# Tapper.net
KiCad netlist of a schematic drawn in EAGLE
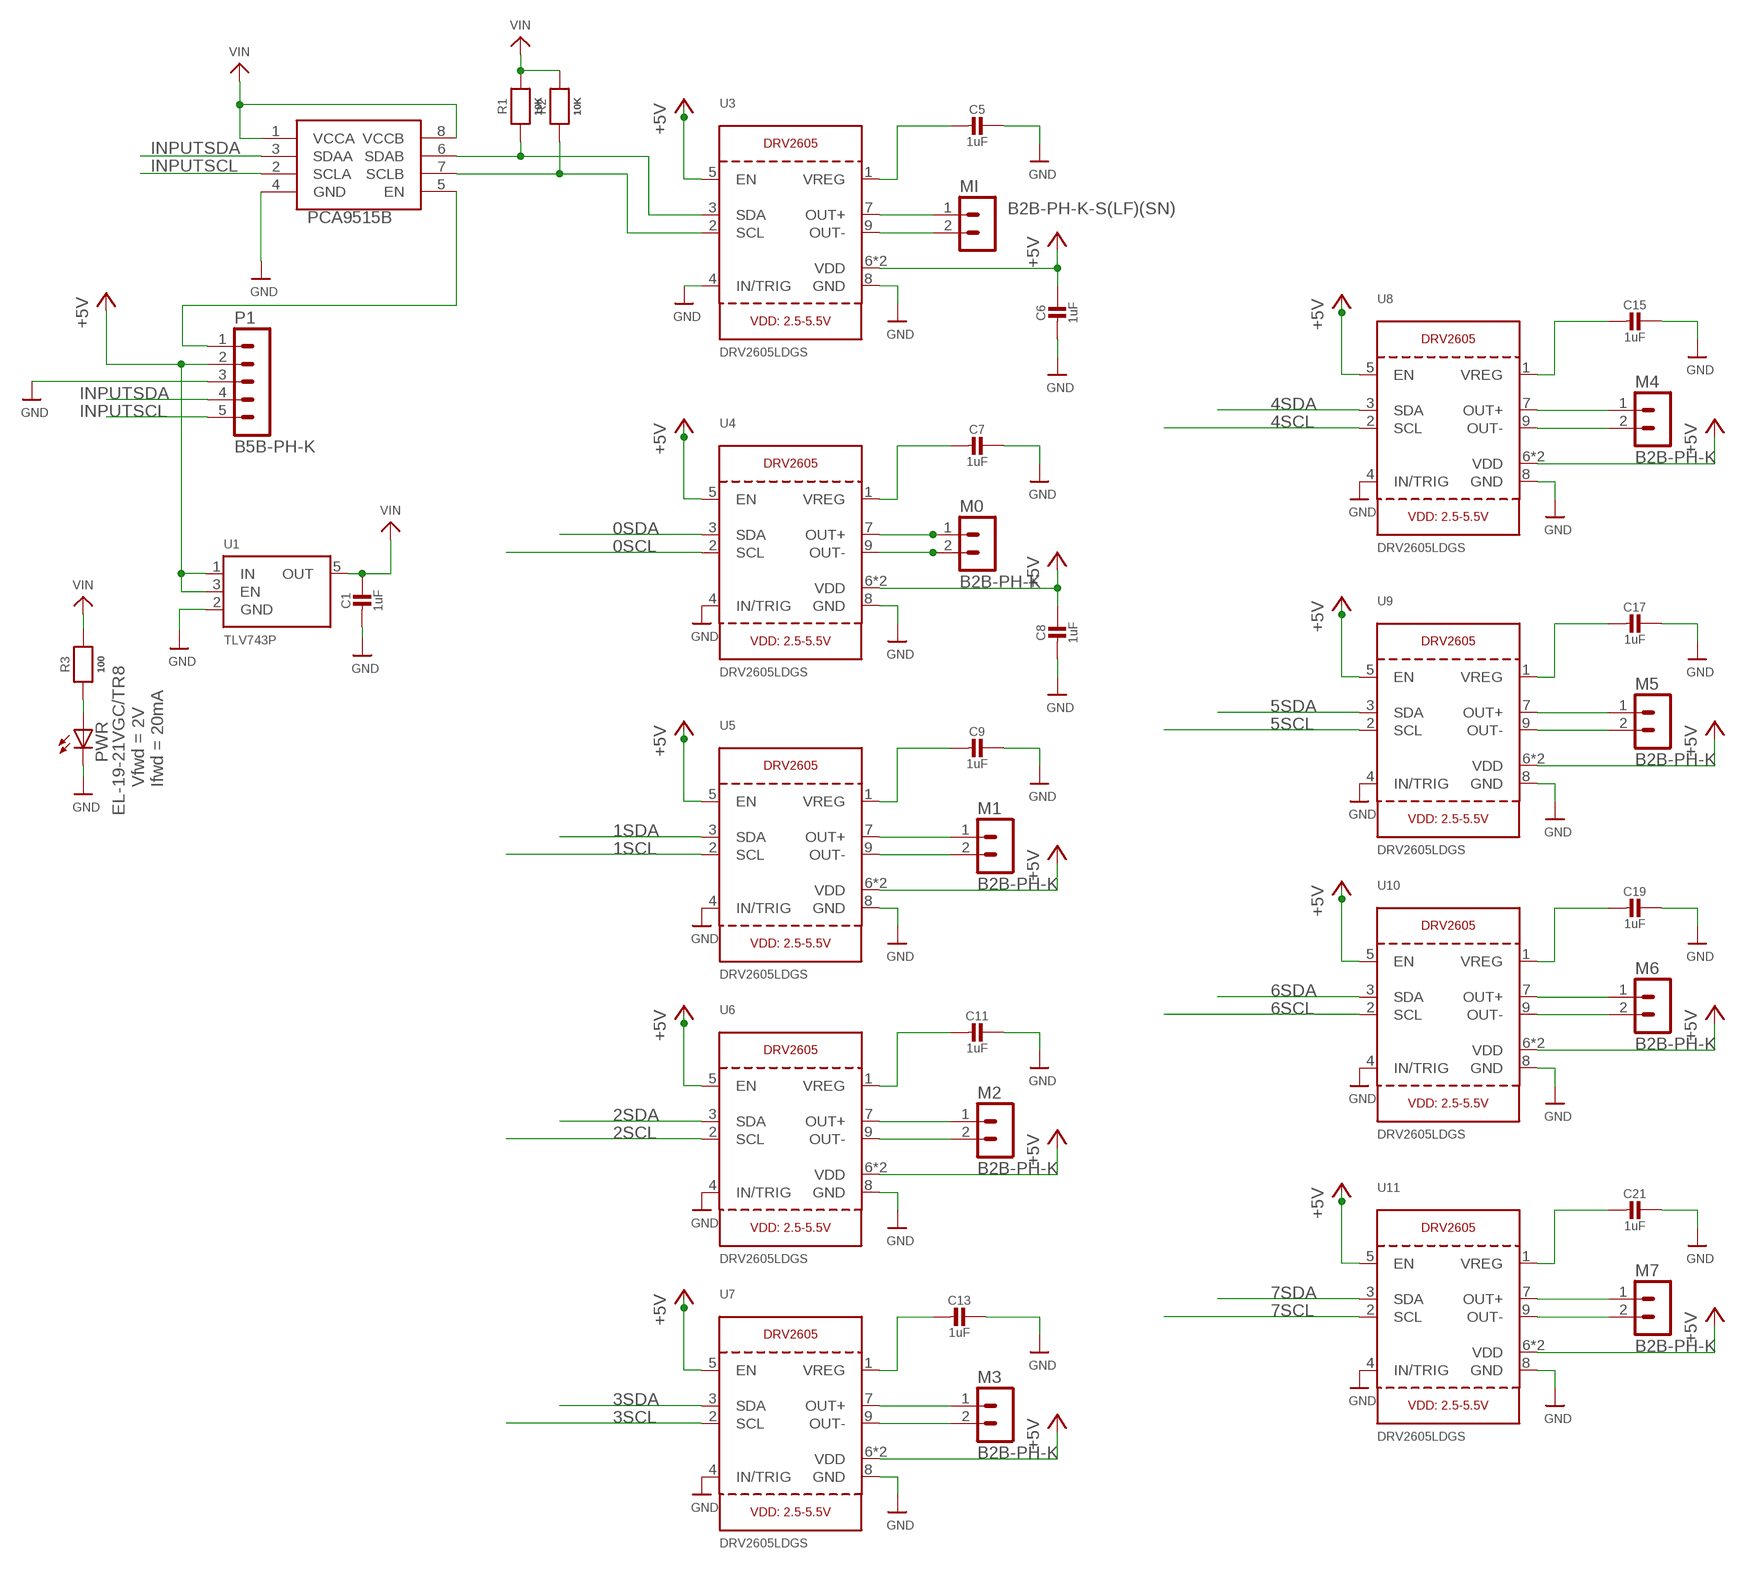
[diagram p0: schematic, sheet 1]
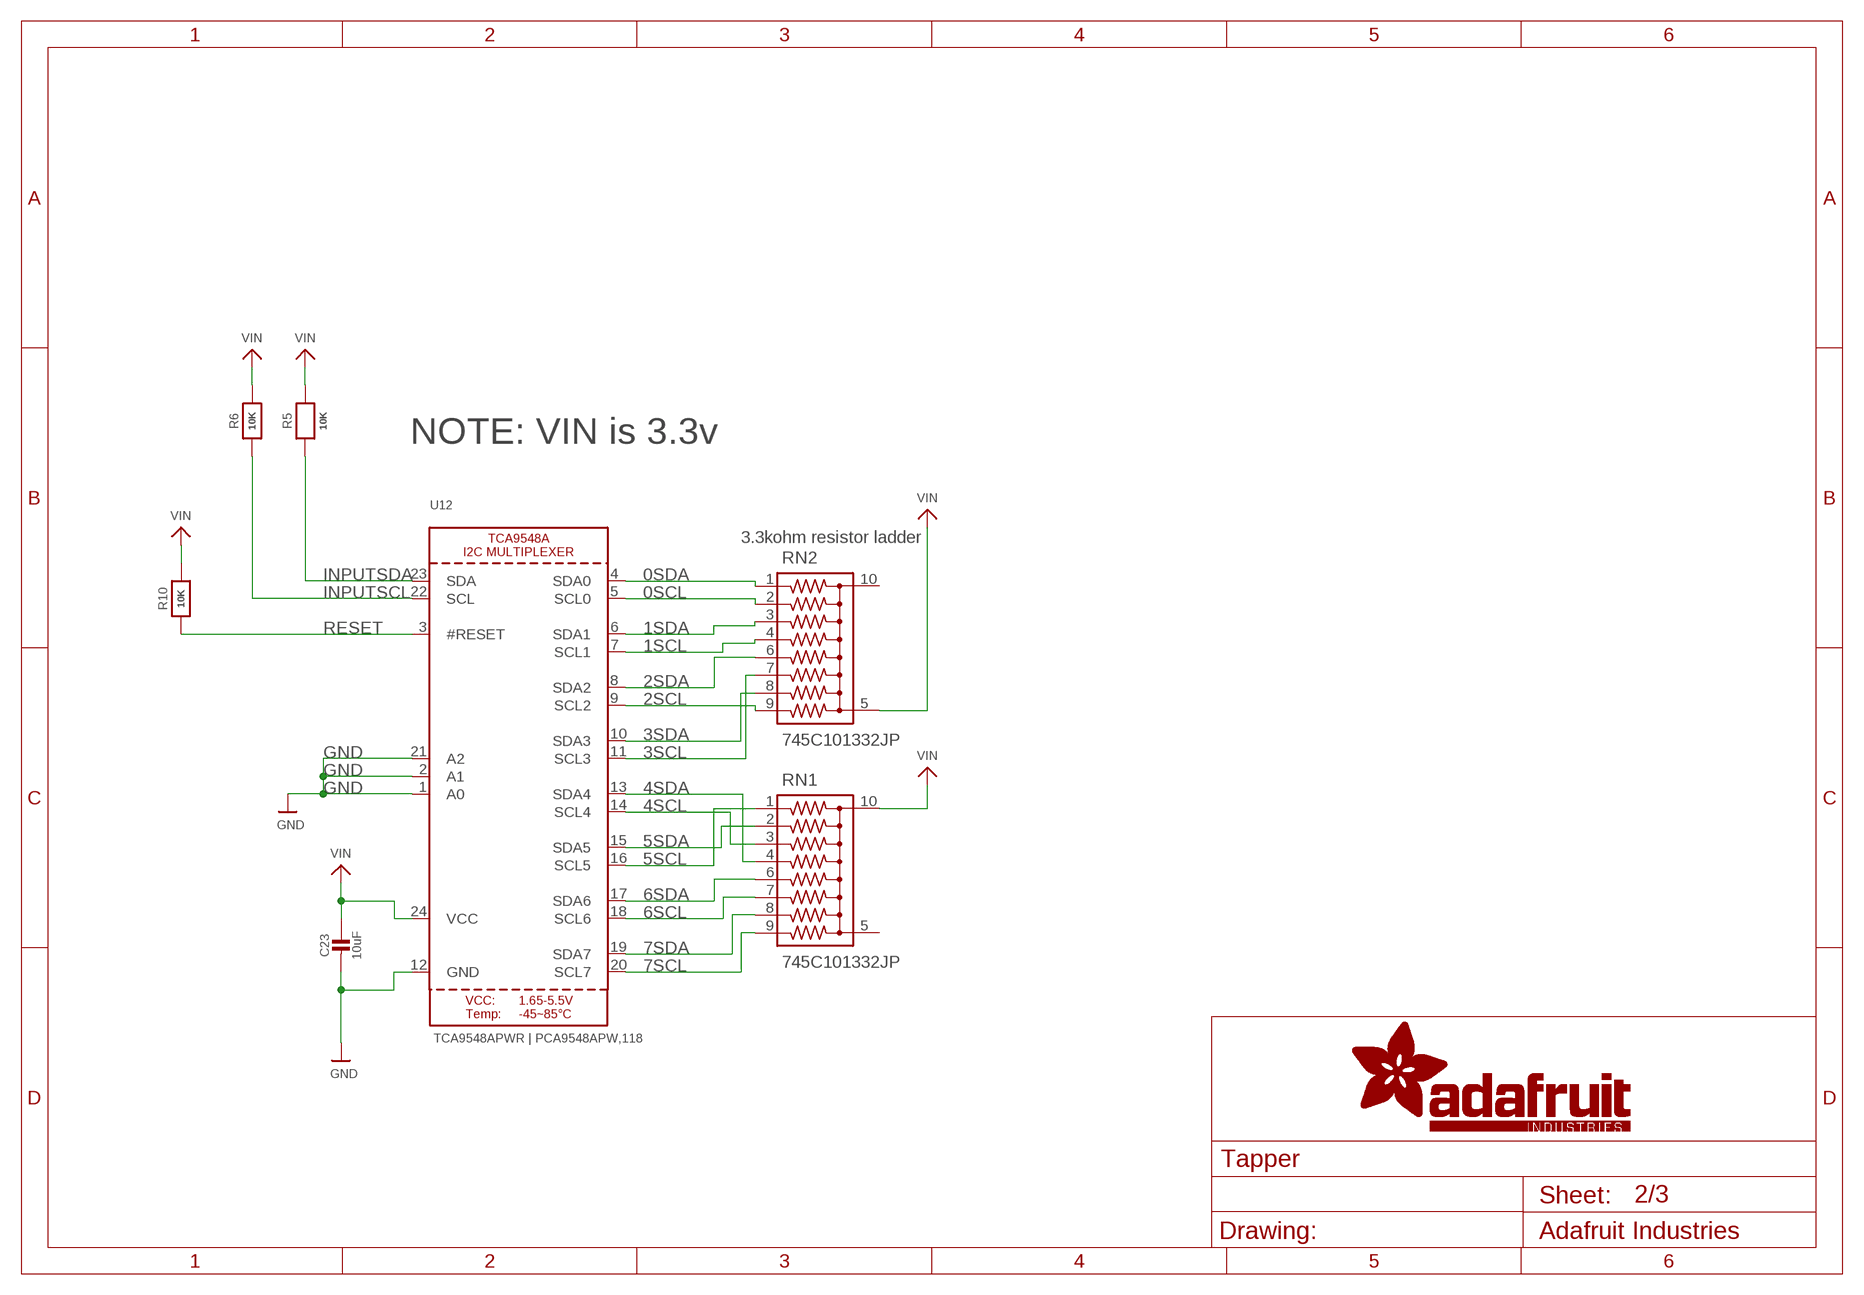
[diagram p1: schematic, sheet 2]

(export (version "E")
  (design (tool "Eeschema 10.0.6"))
  (components
    (comp (ref "C1")
      (value "1uF")
      (footprint "eagle-import:0805-NO")
      (libsource (lib "eagle-import") (part "CAP_CERAMIC0805-NOOUTLINE"))
    )
    (comp (ref "C5")
      (value "1uF")
      (footprint "eagle-import:0805-NO")
      (libsource (lib "eagle-import") (part "CAP_CERAMIC0805-NOOUTLINE"))
    )
    (comp (ref "C6")
      (value "1uF")
      (footprint "eagle-import:0805-NO")
      (libsource (lib "eagle-import") (part "CAP_CERAMIC0805-NOOUTLINE"))
    )
    (comp (ref "C7")
      (value "1uF")
      (footprint "eagle-import:0805-NO")
      (libsource (lib "eagle-import") (part "CAP_CERAMIC0805-NOOUTLINE"))
    )
    (comp (ref "C8")
      (value "1uF")
      (footprint "eagle-import:0805-NO")
      (libsource (lib "eagle-import") (part "CAP_CERAMIC0805-NOOUTLINE"))
    )
    (comp (ref "C9")
      (value "1uF")
      (footprint "eagle-import:0805-NO")
      (libsource (lib "eagle-import") (part "CAP_CERAMIC0805-NOOUTLINE"))
    )
    (comp (ref "C11")
      (value "1uF")
      (footprint "eagle-import:0805-NO")
      (libsource (lib "eagle-import") (part "CAP_CERAMIC0805-NOOUTLINE"))
    )
    (comp (ref "C13")
      (value "1uF")
      (footprint "eagle-import:0805-NO")
      (libsource (lib "eagle-import") (part "CAP_CERAMIC0805-NOOUTLINE"))
    )
    (comp (ref "C15")
      (value "1uF")
      (footprint "eagle-import:0805-NO")
      (libsource (lib "eagle-import") (part "CAP_CERAMIC0805-NOOUTLINE"))
    )
    (comp (ref "C17")
      (value "1uF")
      (footprint "eagle-import:0805-NO")
      (libsource (lib "eagle-import") (part "CAP_CERAMIC0805-NOOUTLINE"))
    )
    (comp (ref "C19")
      (value "1uF")
      (footprint "eagle-import:0805-NO")
      (libsource (lib "eagle-import") (part "CAP_CERAMIC0805-NOOUTLINE"))
    )
    (comp (ref "C21")
      (value "1uF")
      (footprint "eagle-import:0805-NO")
      (libsource (lib "eagle-import") (part "CAP_CERAMIC0805-NOOUTLINE"))
    )
    (comp (ref "M0")
      (value "B2B-PH-K")
      (footprint "eagle-import:B2B-PH-K")
      (libsource (lib "eagle-import") (part "B2B-PH-K"))
    )
    (comp (ref "M1")
      (value "B2B-PH-K")
      (footprint "eagle-import:B2B-PH-K")
      (libsource (lib "eagle-import") (part "B2B-PH-K"))
    )
    (comp (ref "M2")
      (value "B2B-PH-K")
      (footprint "eagle-import:B2B-PH-K")
      (libsource (lib "eagle-import") (part "B2B-PH-K"))
    )
    (comp (ref "M3")
      (value "B2B-PH-K")
      (footprint "eagle-import:B2B-PH-K")
      (libsource (lib "eagle-import") (part "B2B-PH-K"))
    )
    (comp (ref "M4")
      (value "B2B-PH-K")
      (footprint "eagle-import:B2B-PH-K")
      (libsource (lib "eagle-import") (part "B2B-PH-K"))
    )
    (comp (ref "M5")
      (value "B2B-PH-K")
      (footprint "eagle-import:B2B-PH-K")
      (libsource (lib "eagle-import") (part "B2B-PH-K"))
    )
    (comp (ref "M6")
      (value "B2B-PH-K")
      (footprint "eagle-import:B2B-PH-K")
      (libsource (lib "eagle-import") (part "B2B-PH-K"))
    )
    (comp (ref "M7")
      (value "B2B-PH-K")
      (footprint "eagle-import:B2B-PH-K")
      (libsource (lib "eagle-import") (part "B2B-PH-K"))
    )
    (comp (ref "MI")
      (value "B2B-PH-K-S(LF)(SN)")
      (footprint "eagle-import:B2B-PH-K")
      (libsource (lib "eagle-import") (part "B2B-PH-K"))
    )
    (comp (ref "P1")
      (value "B5B-PH-K")
      (footprint "eagle-import:B5B-PH-K")
      (libsource (lib "eagle-import") (part "B5B-PH-K"))
    )
    (comp (ref "PWR")
      (value "EL-19-21VGC/TR8")
      (footprint "eagle-import:CHIP-LED0603")
      (libsource (lib "eagle-import") (part "LEDCHIP-LED0603"))
    )
    (comp (ref "R1")
      (value "10K")
      (footprint "eagle-import:0805-NO")
      (libsource (lib "eagle-import") (part "RESISTOR0805_NOOUTLINE"))
    )
    (comp (ref "R2")
      (value "10K")
      (footprint "eagle-import:0805-NO")
      (libsource (lib "eagle-import") (part "RESISTOR0805_NOOUTLINE"))
    )
    (comp (ref "R3")
      (value "100")
      (footprint "eagle-import:0805-NO")
      (libsource (lib "eagle-import") (part "RESISTOR0805_NOOUTLINE"))
    )
    (comp (ref "U1")
      (value "TLV743P")
      (footprint "eagle-import:SOT23-5")
      (libsource (lib "eagle-import") (part "LD39015XX"))
    )
    (comp (ref "U3")
      (value "DRV2605LDGS")
      (footprint "eagle-import:PSOP10")
      (libsource (lib "eagle-import") (part "DRV2605_SOP"))
    )
    (comp (ref "U4")
      (value "DRV2605LDGS")
      (footprint "eagle-import:PSOP10")
      (libsource (lib "eagle-import") (part "DRV2605_SOP"))
    )
    (comp (ref "U5")
      (value "DRV2605LDGS")
      (footprint "eagle-import:PSOP10")
      (libsource (lib "eagle-import") (part "DRV2605_SOP"))
    )
    (comp (ref "U6")
      (value "DRV2605LDGS")
      (footprint "eagle-import:PSOP10")
      (libsource (lib "eagle-import") (part "DRV2605_SOP"))
    )
    (comp (ref "U7")
      (value "DRV2605LDGS")
      (footprint "eagle-import:PSOP10")
      (libsource (lib "eagle-import") (part "DRV2605_SOP"))
    )
    (comp (ref "U8")
      (value "DRV2605LDGS")
      (footprint "eagle-import:PSOP10")
      (libsource (lib "eagle-import") (part "DRV2605_SOP"))
    )
    (comp (ref "U9")
      (value "DRV2605LDGS")
      (footprint "eagle-import:PSOP10")
      (libsource (lib "eagle-import") (part "DRV2605_SOP"))
    )
    (comp (ref "U10")
      (value "DRV2605LDGS")
      (footprint "eagle-import:PSOP10")
      (libsource (lib "eagle-import") (part "DRV2605_SOP"))
    )
    (comp (ref "U11")
      (value "DRV2605LDGS")
      (footprint "eagle-import:PSOP10")
      (libsource (lib "eagle-import") (part "DRV2605_SOP"))
    )
    (comp (ref "U23")
      (value "PCA9515B")
      (footprint "eagle-import:SO-08")
      (libsource (lib "eagle-import") (part "PCA9517"))
    )
    (comp (ref "C23")
      (value "10uF")
      (footprint "eagle-import:0805-NO")
      (libsource (lib "eagle-import") (part "CAP_CERAMIC0805-NOOUTLINE"))
    )
    (comp (ref "R5")
      (value "10K")
      (footprint "eagle-import:0805-NO")
      (libsource (lib "eagle-import") (part "RESISTOR0805_NOOUTLINE"))
    )
    (comp (ref "R6")
      (value "10K")
      (footprint "eagle-import:0805-NO")
      (libsource (lib "eagle-import") (part "RESISTOR0805_NOOUTLINE"))
    )
    (comp (ref "R10")
      (value "10K")
      (footprint "eagle-import:_0805MP")
      (libsource (lib "eagle-import") (part "RESISTOR_0805MP"))
    )
    (comp (ref "RN1")
      (value "745C101332JP")
      (footprint "eagle-import:745-10NS")
      (libsource (lib "eagle-import") (part "745-10NS"))
    )
    (comp (ref "RN2")
      (value "745C101332JP")
      (footprint "eagle-import:745-10NS")
      (libsource (lib "eagle-import") (part "745-10NS"))
    )
    (comp (ref "U12")
      (value "TCA9548APWR | PCA9548APW,118")
      (footprint "eagle-import:TSSOP24")
      (libsource (lib "eagle-import") (part "TCA9548A"))
    )
  )
  (nets
    (net (code "1") (name "+5V") (class "Default")
      (node (ref "C6") (pin "1") (pinfunction "1_1") (pintype "passive"))
      (node (ref "C8") (pin "1") (pinfunction "1_1") (pintype "passive"))
      (node (ref "P1") (pin "2") (pinfunction "2_2") (pintype "passive"))
      (node (ref "U1") (pin "1") (pinfunction "IN_1") (pintype "bidirectional"))
      (node (ref "U1") (pin "3") (pinfunction "EN_3") (pintype "bidirectional"))
      (node (ref "U10") (pin "10") (pinfunction "VDD_10") (pintype "power_in"))
      (node (ref "U10") (pin "5") (pinfunction "EN_5") (pintype "input"))
      (node (ref "U10") (pin "6") (pinfunction "VDD_6") (pintype "power_in"))
      (node (ref "U11") (pin "10") (pinfunction "VDD_10") (pintype "power_in"))
      (node (ref "U11") (pin "5") (pinfunction "EN_5") (pintype "input"))
      (node (ref "U11") (pin "6") (pinfunction "VDD_6") (pintype "power_in"))
      (node (ref "U3") (pin "10") (pinfunction "VDD_10") (pintype "power_in"))
      (node (ref "U3") (pin "5") (pinfunction "EN_5") (pintype "input"))
      (node (ref "U3") (pin "6") (pinfunction "VDD_6") (pintype "power_in"))
      (node (ref "U4") (pin "10") (pinfunction "VDD_10") (pintype "power_in"))
      (node (ref "U4") (pin "5") (pinfunction "EN_5") (pintype "input"))
      (node (ref "U4") (pin "6") (pinfunction "VDD_6") (pintype "power_in"))
      (node (ref "U5") (pin "10") (pinfunction "VDD_10") (pintype "power_in"))
      (node (ref "U5") (pin "5") (pinfunction "EN_5") (pintype "input"))
      (node (ref "U5") (pin "6") (pinfunction "VDD_6") (pintype "power_in"))
      (node (ref "U6") (pin "10") (pinfunction "VDD_10") (pintype "power_in"))
      (node (ref "U6") (pin "5") (pinfunction "EN_5") (pintype "input"))
      (node (ref "U6") (pin "6") (pinfunction "VDD_6") (pintype "power_in"))
      (node (ref "U7") (pin "10") (pinfunction "VDD_10") (pintype "power_in"))
      (node (ref "U7") (pin "5") (pinfunction "EN_5") (pintype "input"))
      (node (ref "U7") (pin "6") (pinfunction "VDD_6") (pintype "power_in"))
      (node (ref "U8") (pin "10") (pinfunction "VDD_10") (pintype "power_in"))
      (node (ref "U8") (pin "5") (pinfunction "EN_5") (pintype "input"))
      (node (ref "U8") (pin "6") (pinfunction "VDD_6") (pintype "power_in"))
      (node (ref "U9") (pin "10") (pinfunction "VDD_10") (pintype "power_in"))
      (node (ref "U9") (pin "5") (pinfunction "EN_5") (pintype "input"))
      (node (ref "U9") (pin "6") (pinfunction "VDD_6") (pintype "power_in"))
    )
    (net (code "2") (name "0SCL") (class "Default")
      (node (ref "RN2") (pin "2") (pinfunction "2_2") (pintype "passive"))
      (node (ref "U12") (pin "5") (pinfunction "SCL0_5") (pintype "bidirectional"))
      (node (ref "U4") (pin "2") (pinfunction "SCL_2") (pintype "input"))
    )
    (net (code "3") (name "0SDA") (class "Default")
      (node (ref "RN2") (pin "1") (pinfunction "1_1") (pintype "passive"))
      (node (ref "U12") (pin "4") (pinfunction "SDA0_4") (pintype "bidirectional"))
      (node (ref "U4") (pin "3") (pinfunction "SDA_3") (pintype "bidirectional"))
    )
    (net (code "4") (name "1SCL") (class "Default")
      (node (ref "RN2") (pin "4") (pinfunction "4_4") (pintype "passive"))
      (node (ref "U12") (pin "7") (pinfunction "SCL1_7") (pintype "bidirectional"))
      (node (ref "U5") (pin "2") (pinfunction "SCL_2") (pintype "input"))
    )
    (net (code "5") (name "1SDA") (class "Default")
      (node (ref "RN2") (pin "3") (pinfunction "3_3") (pintype "passive"))
      (node (ref "U12") (pin "6") (pinfunction "SDA1_6") (pintype "bidirectional"))
      (node (ref "U5") (pin "3") (pinfunction "SDA_3") (pintype "bidirectional"))
    )
    (net (code "6") (name "2SCL") (class "Default")
      (node (ref "RN2") (pin "9") (pinfunction "9_9") (pintype "passive"))
      (node (ref "U12") (pin "9") (pinfunction "SCL2_9") (pintype "bidirectional"))
      (node (ref "U6") (pin "2") (pinfunction "SCL_2") (pintype "input"))
    )
    (net (code "7") (name "2SDA") (class "Default")
      (node (ref "RN2") (pin "6") (pinfunction "6_6") (pintype "passive"))
      (node (ref "U12") (pin "8") (pinfunction "SDA2_8") (pintype "bidirectional"))
      (node (ref "U6") (pin "3") (pinfunction "SDA_3") (pintype "bidirectional"))
    )
    (net (code "8") (name "3SCL") (class "Default")
      (node (ref "RN2") (pin "7") (pinfunction "7_7") (pintype "passive"))
      (node (ref "U12") (pin "11") (pinfunction "SCL3_11") (pintype "bidirectional"))
      (node (ref "U7") (pin "2") (pinfunction "SCL_2") (pintype "input"))
    )
    (net (code "9") (name "3SDA") (class "Default")
      (node (ref "RN2") (pin "8") (pinfunction "8_8") (pintype "passive"))
      (node (ref "U12") (pin "10") (pinfunction "SDA3_10") (pintype "bidirectional"))
      (node (ref "U7") (pin "3") (pinfunction "SDA_3") (pintype "bidirectional"))
    )
    (net (code "10") (name "4SCL") (class "Default")
      (node (ref "RN1") (pin "3") (pinfunction "3_3") (pintype "passive"))
      (node (ref "U12") (pin "14") (pinfunction "SCL4_14") (pintype "bidirectional"))
      (node (ref "U8") (pin "2") (pinfunction "SCL_2") (pintype "input"))
    )
    (net (code "11") (name "4SDA") (class "Default")
      (node (ref "RN1") (pin "4") (pinfunction "4_4") (pintype "passive"))
      (node (ref "U12") (pin "13") (pinfunction "SDA4_13") (pintype "bidirectional"))
      (node (ref "U8") (pin "3") (pinfunction "SDA_3") (pintype "bidirectional"))
    )
    (net (code "12") (name "5SCL") (class "Default")
      (node (ref "RN1") (pin "1") (pinfunction "1_1") (pintype "passive"))
      (node (ref "U12") (pin "16") (pinfunction "SCL5_16") (pintype "bidirectional"))
      (node (ref "U9") (pin "2") (pinfunction "SCL_2") (pintype "input"))
    )
    (net (code "13") (name "5SDA") (class "Default")
      (node (ref "RN1") (pin "2") (pinfunction "2_2") (pintype "passive"))
      (node (ref "U12") (pin "15") (pinfunction "SDA5_15") (pintype "bidirectional"))
      (node (ref "U9") (pin "3") (pinfunction "SDA_3") (pintype "bidirectional"))
    )
    (net (code "14") (name "6SCL") (class "Default")
      (node (ref "RN1") (pin "7") (pinfunction "7_7") (pintype "passive"))
      (node (ref "U10") (pin "2") (pinfunction "SCL_2") (pintype "input"))
      (node (ref "U12") (pin "18") (pinfunction "SCL6_18") (pintype "bidirectional"))
    )
    (net (code "15") (name "6SDA") (class "Default")
      (node (ref "RN1") (pin "6") (pinfunction "6_6") (pintype "passive"))
      (node (ref "U10") (pin "3") (pinfunction "SDA_3") (pintype "bidirectional"))
      (node (ref "U12") (pin "17") (pinfunction "SDA6_17") (pintype "bidirectional"))
    )
    (net (code "16") (name "7SCL") (class "Default")
      (node (ref "RN1") (pin "9") (pinfunction "9_9") (pintype "passive"))
      (node (ref "U11") (pin "2") (pinfunction "SCL_2") (pintype "input"))
      (node (ref "U12") (pin "20") (pinfunction "SCL7_20") (pintype "bidirectional"))
    )
    (net (code "17") (name "7SDA") (class "Default")
      (node (ref "RN1") (pin "8") (pinfunction "8_8") (pintype "passive"))
      (node (ref "U11") (pin "3") (pinfunction "SDA_3") (pintype "bidirectional"))
      (node (ref "U12") (pin "19") (pinfunction "SDA7_19") (pintype "bidirectional"))
    )
    (net (code "18") (name "GND") (class "Default")
      (node (ref "C1") (pin "2") (pinfunction "2_2") (pintype "passive"))
      (node (ref "C11") (pin "1") (pinfunction "1_1") (pintype "passive"))
      (node (ref "C13") (pin "1") (pinfunction "1_1") (pintype "passive"))
      (node (ref "C15") (pin "1") (pinfunction "1_1") (pintype "passive"))
      (node (ref "C17") (pin "1") (pinfunction "1_1") (pintype "passive"))
      (node (ref "C19") (pin "1") (pinfunction "1_1") (pintype "passive"))
      (node (ref "C21") (pin "1") (pinfunction "1_1") (pintype "passive"))
      (node (ref "C23") (pin "2") (pinfunction "2_2") (pintype "passive"))
      (node (ref "C5") (pin "1") (pinfunction "1_1") (pintype "passive"))
      (node (ref "C6") (pin "2") (pinfunction "2_2") (pintype "passive"))
      (node (ref "C7") (pin "1") (pinfunction "1_1") (pintype "passive"))
      (node (ref "C8") (pin "2") (pinfunction "2_2") (pintype "passive"))
      (node (ref "C9") (pin "1") (pinfunction "1_1") (pintype "passive"))
      (node (ref "P1") (pin "3") (pinfunction "3_3") (pintype "passive"))
      (node (ref "PWR") (pin "C") (pinfunction "C_C") (pintype "passive"))
      (node (ref "U1") (pin "2") (pinfunction "GND_2") (pintype "bidirectional"))
      (node (ref "U10") (pin "4") (pinfunction "IN/TRIG_4") (pintype "input"))
      (node (ref "U10") (pin "8") (pinfunction "GND_8") (pintype "power_in"))
      (node (ref "U11") (pin "4") (pinfunction "IN/TRIG_4") (pintype "input"))
      (node (ref "U11") (pin "8") (pinfunction "GND_8") (pintype "power_in"))
      (node (ref "U12") (pin "1") (pinfunction "A0_1") (pintype "bidirectional"))
      (node (ref "U12") (pin "12") (pinfunction "GND_12") (pintype "bidirectional"))
      (node (ref "U12") (pin "2") (pinfunction "A1_2") (pintype "bidirectional"))
      (node (ref "U12") (pin "21") (pinfunction "A2_21") (pintype "bidirectional"))
      (node (ref "U23") (pin "4") (pinfunction "GND_4") (pintype "bidirectional"))
      (node (ref "U3") (pin "4") (pinfunction "IN/TRIG_4") (pintype "input"))
      (node (ref "U3") (pin "8") (pinfunction "GND_8") (pintype "power_in"))
      (node (ref "U4") (pin "4") (pinfunction "IN/TRIG_4") (pintype "input"))
      (node (ref "U4") (pin "8") (pinfunction "GND_8") (pintype "power_in"))
      (node (ref "U5") (pin "4") (pinfunction "IN/TRIG_4") (pintype "input"))
      (node (ref "U5") (pin "8") (pinfunction "GND_8") (pintype "power_in"))
      (node (ref "U6") (pin "4") (pinfunction "IN/TRIG_4") (pintype "input"))
      (node (ref "U6") (pin "8") (pinfunction "GND_8") (pintype "power_in"))
      (node (ref "U7") (pin "4") (pinfunction "IN/TRIG_4") (pintype "input"))
      (node (ref "U7") (pin "8") (pinfunction "GND_8") (pintype "power_in"))
      (node (ref "U8") (pin "4") (pinfunction "IN/TRIG_4") (pintype "input"))
      (node (ref "U8") (pin "8") (pinfunction "GND_8") (pintype "power_in"))
      (node (ref "U9") (pin "4") (pinfunction "IN/TRIG_4") (pintype "input"))
      (node (ref "U9") (pin "8") (pinfunction "GND_8") (pintype "power_in"))
    )
    (net (code "19") (name "INPUTSCL") (class "Default")
      (node (ref "P1") (pin "5") (pinfunction "5_5") (pintype "passive"))
      (node (ref "R6") (pin "1") (pinfunction "1_1") (pintype "passive"))
      (node (ref "U12") (pin "22") (pinfunction "SCL_22") (pintype "bidirectional"))
      (node (ref "U23") (pin "2") (pinfunction "SCLA_2") (pintype "bidirectional"))
    )
    (net (code "20") (name "INPUTSDA") (class "Default")
      (node (ref "P1") (pin "4") (pinfunction "4_4") (pintype "passive"))
      (node (ref "R5") (pin "1") (pinfunction "1_1") (pintype "passive"))
      (node (ref "U12") (pin "23") (pinfunction "SDA_23") (pintype "bidirectional"))
      (node (ref "U23") (pin "3") (pinfunction "SDAA_3") (pintype "bidirectional"))
    )
    (net (code "21") (name "Net-(PWR-PadA)") (class "Default")
      (node (ref "PWR") (pin "A") (pinfunction "A_A") (pintype "passive"))
      (node (ref "R3") (pin "1") (pinfunction "1_1") (pintype "passive"))
    )
    (net (code "22") (name "Net-(U3-OUT+)") (class "Default")
      (node (ref "MI") (pin "1") (pinfunction "1_1") (pintype "passive"))
      (node (ref "U3") (pin "7") (pinfunction "OUT+_7") (pintype "output"))
    )
    (net (code "23") (name "Net-(U3-OUT-)") (class "Default")
      (node (ref "MI") (pin "2") (pinfunction "2_2") (pintype "passive"))
      (node (ref "U3") (pin "9") (pinfunction "OUT-_9") (pintype "output"))
    )
    (net (code "24") (name "Net-(U3-VREG)") (class "Default")
      (node (ref "C5") (pin "2") (pinfunction "2_2") (pintype "passive"))
      (node (ref "U3") (pin "1") (pinfunction "VREG_1") (pintype "output"))
    )
    (net (code "25") (name "Net-(U4-OUT+)") (class "Default")
      (node (ref "M0") (pin "1") (pinfunction "1_1") (pintype "passive"))
      (node (ref "U4") (pin "7") (pinfunction "OUT+_7") (pintype "output"))
    )
    (net (code "26") (name "Net-(U4-OUT-)") (class "Default")
      (node (ref "M0") (pin "2") (pinfunction "2_2") (pintype "passive"))
      (node (ref "U4") (pin "9") (pinfunction "OUT-_9") (pintype "output"))
    )
    (net (code "27") (name "Net-(U4-VREG)") (class "Default")
      (node (ref "C7") (pin "2") (pinfunction "2_2") (pintype "passive"))
      (node (ref "U4") (pin "1") (pinfunction "VREG_1") (pintype "output"))
    )
    (net (code "28") (name "Net-(U5-OUT+)") (class "Default")
      (node (ref "M1") (pin "1") (pinfunction "1_1") (pintype "passive"))
      (node (ref "U5") (pin "7") (pinfunction "OUT+_7") (pintype "output"))
    )
    (net (code "29") (name "Net-(U5-OUT-)") (class "Default")
      (node (ref "M1") (pin "2") (pinfunction "2_2") (pintype "passive"))
      (node (ref "U5") (pin "9") (pinfunction "OUT-_9") (pintype "output"))
    )
    (net (code "30") (name "Net-(U5-VREG)") (class "Default")
      (node (ref "C9") (pin "2") (pinfunction "2_2") (pintype "passive"))
      (node (ref "U5") (pin "1") (pinfunction "VREG_1") (pintype "output"))
    )
    (net (code "31") (name "Net-(U6-OUT+)") (class "Default")
      (node (ref "M2") (pin "1") (pinfunction "1_1") (pintype "passive"))
      (node (ref "U6") (pin "7") (pinfunction "OUT+_7") (pintype "output"))
    )
    (net (code "32") (name "Net-(U6-OUT-)") (class "Default")
      (node (ref "M2") (pin "2") (pinfunction "2_2") (pintype "passive"))
      (node (ref "U6") (pin "9") (pinfunction "OUT-_9") (pintype "output"))
    )
    (net (code "33") (name "Net-(U6-VREG)") (class "Default")
      (node (ref "C11") (pin "2") (pinfunction "2_2") (pintype "passive"))
      (node (ref "U6") (pin "1") (pinfunction "VREG_1") (pintype "output"))
    )
    (net (code "34") (name "Net-(U7-OUT+)") (class "Default")
      (node (ref "M3") (pin "1") (pinfunction "1_1") (pintype "passive"))
      (node (ref "U7") (pin "7") (pinfunction "OUT+_7") (pintype "output"))
    )
    (net (code "35") (name "Net-(U7-OUT-)") (class "Default")
      (node (ref "M3") (pin "2") (pinfunction "2_2") (pintype "passive"))
      (node (ref "U7") (pin "9") (pinfunction "OUT-_9") (pintype "output"))
    )
    (net (code "36") (name "Net-(U7-VREG)") (class "Default")
      (node (ref "C13") (pin "2") (pinfunction "2_2") (pintype "passive"))
      (node (ref "U7") (pin "1") (pinfunction "VREG_1") (pintype "output"))
    )
    (net (code "37") (name "Net-(U8-OUT+)") (class "Default")
      (node (ref "M4") (pin "1") (pinfunction "1_1") (pintype "passive"))
      (node (ref "U8") (pin "7") (pinfunction "OUT+_7") (pintype "output"))
    )
    (net (code "38") (name "Net-(U8-OUT-)") (class "Default")
      (node (ref "M4") (pin "2") (pinfunction "2_2") (pintype "passive"))
      (node (ref "U8") (pin "9") (pinfunction "OUT-_9") (pintype "output"))
    )
    (net (code "39") (name "Net-(U8-VREG)") (class "Default")
      (node (ref "C15") (pin "2") (pinfunction "2_2") (pintype "passive"))
      (node (ref "U8") (pin "1") (pinfunction "VREG_1") (pintype "output"))
    )
    (net (code "40") (name "Net-(U9-OUT+)") (class "Default")
      (node (ref "M5") (pin "1") (pinfunction "1_1") (pintype "passive"))
      (node (ref "U9") (pin "7") (pinfunction "OUT+_7") (pintype "output"))
    )
    (net (code "41") (name "Net-(U9-OUT-)") (class "Default")
      (node (ref "M5") (pin "2") (pinfunction "2_2") (pintype "passive"))
      (node (ref "U9") (pin "9") (pinfunction "OUT-_9") (pintype "output"))
    )
    (net (code "42") (name "Net-(U9-VREG)") (class "Default")
      (node (ref "C17") (pin "2") (pinfunction "2_2") (pintype "passive"))
      (node (ref "U9") (pin "1") (pinfunction "VREG_1") (pintype "output"))
    )
    (net (code "43") (name "Net-(U10-OUT+)") (class "Default")
      (node (ref "M6") (pin "1") (pinfunction "1_1") (pintype "passive"))
      (node (ref "U10") (pin "7") (pinfunction "OUT+_7") (pintype "output"))
    )
    (net (code "44") (name "Net-(U10-OUT-)") (class "Default")
      (node (ref "M6") (pin "2") (pinfunction "2_2") (pintype "passive"))
      (node (ref "U10") (pin "9") (pinfunction "OUT-_9") (pintype "output"))
    )
    (net (code "45") (name "Net-(U10-VREG)") (class "Default")
      (node (ref "C19") (pin "2") (pinfunction "2_2") (pintype "passive"))
      (node (ref "U10") (pin "1") (pinfunction "VREG_1") (pintype "output"))
    )
    (net (code "46") (name "Net-(U11-OUT+)") (class "Default")
      (node (ref "M7") (pin "1") (pinfunction "1_1") (pintype "passive"))
      (node (ref "U11") (pin "7") (pinfunction "OUT+_7") (pintype "output"))
    )
    (net (code "47") (name "Net-(U11-OUT-)") (class "Default")
      (node (ref "M7") (pin "2") (pinfunction "2_2") (pintype "passive"))
      (node (ref "U11") (pin "9") (pinfunction "OUT-_9") (pintype "output"))
    )
    (net (code "48") (name "Net-(U11-VREG)") (class "Default")
      (node (ref "C21") (pin "2") (pinfunction "2_2") (pintype "passive"))
      (node (ref "U11") (pin "1") (pinfunction "VREG_1") (pintype "output"))
    )
    (net (code "49") (name "Net-(U23-EN)") (class "Default")
      (node (ref "P1") (pin "1") (pinfunction "1_1") (pintype "passive"))
      (node (ref "U23") (pin "5") (pinfunction "EN_5") (pintype "bidirectional"))
    )
    (net (code "50") (name "Net-(U23-SCLB)") (class "Default")
      (node (ref "R2") (pin "1") (pinfunction "1_1") (pintype "passive"))
      (node (ref "U23") (pin "7") (pinfunction "SCLB_7") (pintype "bidirectional"))
      (node (ref "U3") (pin "2") (pinfunction "SCL_2") (pintype "input"))
    )
    (net (code "51") (name "Net-(U23-SDAB)") (class "Default")
      (node (ref "R1") (pin "1") (pinfunction "1_1") (pintype "passive"))
      (node (ref "U23") (pin "6") (pinfunction "SDAB_6") (pintype "bidirectional"))
      (node (ref "U3") (pin "3") (pinfunction "SDA_3") (pintype "bidirectional"))
    )
    (net (code "52") (name "RESET") (class "Default")
      (node (ref "R10") (pin "1") (pinfunction "1_1") (pintype "passive"))
      (node (ref "U12") (pin "3") (pinfunction "#RESET_3") (pintype "bidirectional"))
    )
    (net (code "53") (name "VIN") (class "Default")
      (node (ref "C1") (pin "1") (pinfunction "1_1") (pintype "passive"))
      (node (ref "C23") (pin "1") (pinfunction "1_1") (pintype "passive"))
      (node (ref "R1") (pin "2") (pinfunction "2_2") (pintype "passive"))
      (node (ref "R10") (pin "2") (pinfunction "2_2") (pintype "passive"))
      (node (ref "R2") (pin "2") (pinfunction "2_2") (pintype "passive"))
      (node (ref "R3") (pin "2") (pinfunction "2_2") (pintype "passive"))
      (node (ref "R5") (pin "2") (pinfunction "2_2") (pintype "passive"))
      (node (ref "R6") (pin "2") (pinfunction "2_2") (pintype "passive"))
      (node (ref "RN1") (pin "10") (pinfunction "10_10") (pintype "passive"))
      (node (ref "RN2") (pin "5") (pinfunction "5_5") (pintype "passive"))
      (node (ref "U1") (pin "5") (pinfunction "OUT_5") (pintype "bidirectional"))
      (node (ref "U12") (pin "24") (pinfunction "VCC_24") (pintype "bidirectional"))
      (node (ref "U23") (pin "1") (pinfunction "VCCA_1") (pintype "bidirectional"))
      (node (ref "U23") (pin "8") (pinfunction "VCCB_8") (pintype "bidirectional"))
    )
    (net (code "54") (name "unconnected-(RN1-Pad5)") (class "Default")
      (node (ref "RN1") (pin "5") (pinfunction "5_5") (pintype "passive"))
    )
    (net (code "55") (name "unconnected-(RN2-Pad10)") (class "Default")
      (node (ref "RN2") (pin "10") (pinfunction "10_10") (pintype "passive"))
    )
  )
)
